# GankenKunCircuit.net
KiCad netlist of a schematic drawn in EAGLE
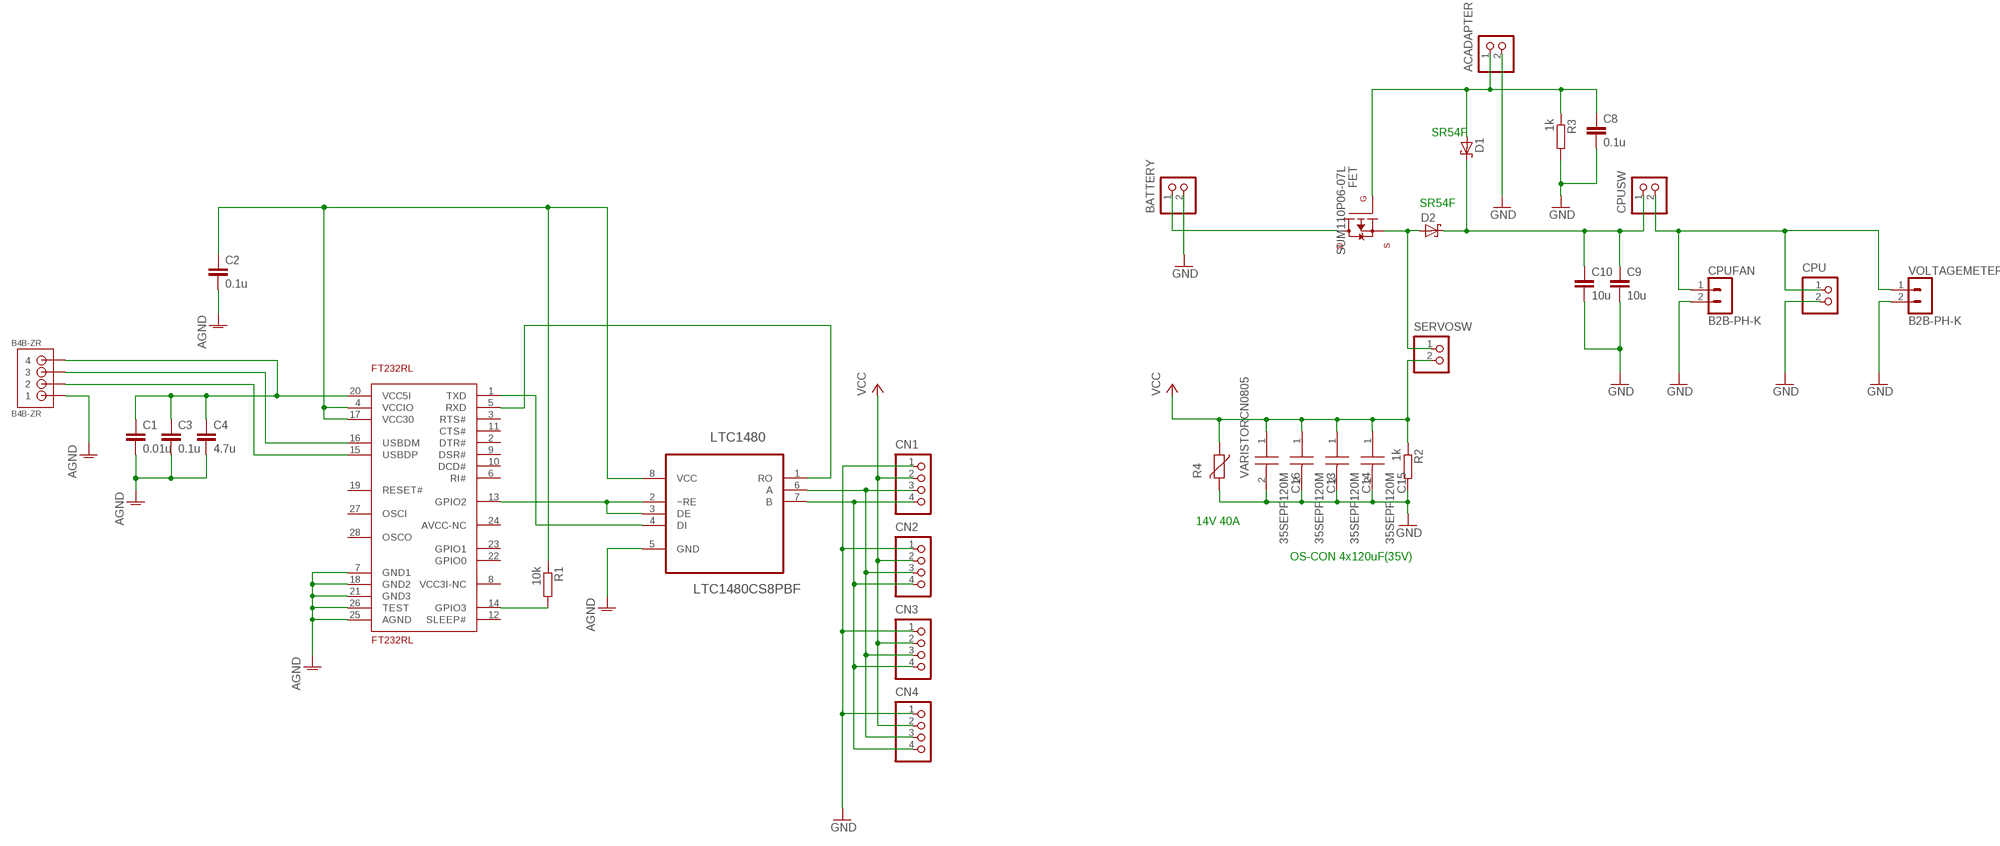
[diagram p0: schematic, sheet 1]

(export (version "E")
  (design (tool "Eeschema 10.0.6"))
  (components
    (comp (ref "ACADAPTER")
      (value "B2B-XH-A")
      (footprint "eagle-import:B2B-XH-A")
      (libsource (lib "eagle-import") (part "B2B-XH-A"))
    )
    (comp (ref "B4B-ZR")
      (value "B4B-ZR")
      (footprint "eagle-import:B4B-ZR")
      (libsource (lib "eagle-import") (part "B4B-ZR"))
    )
    (comp (ref "BATTERY")
      (value "B2P-VH")
      (footprint "eagle-import:B2P-VH")
      (libsource (lib "eagle-import") (part "B2P-VH"))
    )
    (comp (ref "C1")
      (value "0.01u")
      (footprint "eagle-import:C2012")
      (libsource (lib "eagle-import") (part "C-EUC2012"))
    )
    (comp (ref "C2")
      (value "0.1u")
      (footprint "eagle-import:C2012")
      (libsource (lib "eagle-import") (part "C-EUC2012"))
    )
    (comp (ref "C3")
      (value "0.1u")
      (footprint "eagle-import:C2012")
      (libsource (lib "eagle-import") (part "C-EUC2012"))
    )
    (comp (ref "C4")
      (value "4.7u")
      (footprint "eagle-import:C2012")
      (libsource (lib "eagle-import") (part "C-EUC2012"))
    )
    (comp (ref "C8")
      (value "0.1u")
      (footprint "eagle-import:C2012")
      (libsource (lib "eagle-import") (part "C-EUC2012"))
    )
    (comp (ref "C9")
      (value "10u")
      (footprint "eagle-import:C3216")
      (libsource (lib "eagle-import") (part "C-EUC3216"))
    )
    (comp (ref "C10")
      (value "10u")
      (footprint "eagle-import:C3216")
      (libsource (lib "eagle-import") (part "C-EUC3216"))
    )
    (comp (ref "C13")
      (value "35SEPF120M")
      (footprint "eagle-import:CAPPRD500W65D1000H1350")
      (fields (field (name "MOUSER_PART_NUMBER") "667-35SEPF120M") (field (name "RS_PART_NUMBER") "1000082"))
      (libsource (lib "eagle-import") (part "35SEPF120M"))
    )
    (comp (ref "C14")
      (value "35SEPF120M")
      (footprint "eagle-import:CAPPRD500W65D1000H1350")
      (fields (field (name "MOUSER_PART_NUMBER") "667-35SEPF120M") (field (name "RS_PART_NUMBER") "1000082"))
      (libsource (lib "eagle-import") (part "35SEPF120M"))
    )
    (comp (ref "C15")
      (value "35SEPF120M")
      (footprint "eagle-import:CAPPRD500W65D1000H1350")
      (fields (field (name "MOUSER_PART_NUMBER") "667-35SEPF120M") (field (name "RS_PART_NUMBER") "1000082"))
      (libsource (lib "eagle-import") (part "35SEPF120M"))
    )
    (comp (ref "C16")
      (value "35SEPF120M")
      (footprint "eagle-import:CAPPRD500W65D1000H1350")
      (fields (field (name "MOUSER_PART_NUMBER") "667-35SEPF120M") (field (name "RS_PART_NUMBER") "1000082"))
      (libsource (lib "eagle-import") (part "35SEPF120M"))
    )
    (comp (ref "CN1")
      (value "B4B-XH-A")
      (footprint "eagle-import:B4B-XH-A")
      (libsource (lib "eagle-import") (part "B4B-XH-A"))
    )
    (comp (ref "CN2")
      (value "B4B-XH-A")
      (footprint "eagle-import:B4B-XH-A")
      (libsource (lib "eagle-import") (part "B4B-XH-A"))
    )
    (comp (ref "CN3")
      (value "B4B-XH-A")
      (footprint "eagle-import:B4B-XH-A")
      (libsource (lib "eagle-import") (part "B4B-XH-A"))
    )
    (comp (ref "CN4")
      (value "B4B-XH-A")
      (footprint "eagle-import:B4B-XH-A")
      (libsource (lib "eagle-import") (part "B4B-XH-A"))
    )
    (comp (ref "CPU")
      (value "B2B-XH-A")
      (footprint "eagle-import:B2B-XH-A")
      (libsource (lib "eagle-import") (part "B2B-XH-A"))
    )
    (comp (ref "CPUFAN")
      (value "B2B-PH-K")
      (footprint "eagle-import:B2B-PH-K")
      (libsource (lib "eagle-import") (part "B2B-PH-K"))
    )
    (comp (ref "CPUSW")
      (value "B2B-XH-A")
      (footprint "eagle-import:B2B-XH-A")
      (libsource (lib "eagle-import") (part "B2B-XH-A"))
    )
    (comp (ref "D1")
      (value "SCHOTTKY-DIODESMD")
      (footprint "eagle-import:SMB")
      (libsource (lib "eagle-import") (part "SCHOTTKY-DIODESMD"))
    )
    (comp (ref "D2")
      (value "SCHOTTKY-DIODESMD")
      (footprint "eagle-import:SMB")
      (libsource (lib "eagle-import") (part "SCHOTTKY-DIODESMD"))
    )
    (comp (ref "FET")
      (value "SUM110P06-07L")
      (footprint "eagle-import:TO-263-2")
      (fields (field (name "MF") "Vishay"))
      (libsource (lib "eagle-import") (part "SUM110P06-07L"))
    )
    (comp (ref "FT232RL")
      (value "FT232RL")
      (footprint "eagle-import:SSOP28")
      (fields (field (name "MF") "FTDI"))
      (libsource (lib "eagle-import") (part "FT232RL"))
    )
    (comp (ref "LTC1480")
      (value "LTC1480CS8PBF")
      (footprint "eagle-import:SOIC127P600X175-8N")
      (fields (field (name "MF") "Linear Technology/Analog") (field (name "MP") "LTC1480CS8#PBF"))
      (libsource (lib "eagle-import") (part "LTC1480CS8PBF"))
    )
    (comp (ref "R1")
      (value "10k")
      (footprint "eagle-import:M2012")
      (libsource (lib "eagle-import") (part "R-EU_M2012"))
    )
    (comp (ref "R2")
      (value "1k")
      (footprint "eagle-import:M2012")
      (libsource (lib "eagle-import") (part "R-EU_M2012"))
    )
    (comp (ref "R3")
      (value "1k")
      (footprint "eagle-import:M2012")
      (libsource (lib "eagle-import") (part "R-EU_M2012"))
    )
    (comp (ref "R4")
      (value "VARISTORCN0805")
      (footprint "eagle-import:CT_CN0805")
      (libsource (lib "eagle-import") (part "VARISTORCN0805"))
    )
    (comp (ref "SERVOSW")
      (value "B2P-VH")
      (footprint "eagle-import:B2P-VH")
      (libsource (lib "eagle-import") (part "B2P-VH"))
    )
    (comp (ref "VOLTAGEMETER")
      (value "B2B-PH-K")
      (footprint "eagle-import:B2B-PH-K")
      (libsource (lib "eagle-import") (part "B2B-PH-K"))
    )
  )
  (nets
    (net (code "1") (name "AGND") (class "Default")
      (node (ref "B4B-ZR") (pin "1") (pinfunction "1_1") (pintype "bidirectional"))
      (node (ref "C1") (pin "2") (pinfunction "2_2") (pintype "passive"))
      (node (ref "C2") (pin "2") (pinfunction "2_2") (pintype "passive"))
      (node (ref "C3") (pin "2") (pinfunction "2_2") (pintype "passive"))
      (node (ref "C4") (pin "2") (pinfunction "2_2") (pintype "passive"))
      (node (ref "FT232RL") (pin "18") (pinfunction "GND2_18") (pintype "power_in"))
      (node (ref "FT232RL") (pin "21") (pinfunction "GND3_21") (pintype "power_in"))
      (node (ref "FT232RL") (pin "25") (pinfunction "AGND_25") (pintype "power_in"))
      (node (ref "FT232RL") (pin "26") (pinfunction "TEST_26") (pintype "input"))
      (node (ref "FT232RL") (pin "7") (pinfunction "GND1_7") (pintype "power_in"))
      (node (ref "LTC1480") (pin "5") (pinfunction "GND_5") (pintype "passive"))
    )
    (net (code "2") (name "GND") (class "Default")
      (node (ref "ACADAPTER") (pin "2") (pinfunction "2_2") (pintype "passive"))
      (node (ref "BATTERY") (pin "2") (pinfunction "2_2") (pintype "passive"))
      (node (ref "C10") (pin "2") (pinfunction "2_2") (pintype "passive"))
      (node (ref "C13") (pin "2") (pinfunction "-_2") (pintype "bidirectional"))
      (node (ref "C14") (pin "2") (pinfunction "-_2") (pintype "bidirectional"))
      (node (ref "C15") (pin "2") (pinfunction "-_2") (pintype "bidirectional"))
      (node (ref "C16") (pin "2") (pinfunction "-_2") (pintype "bidirectional"))
      (node (ref "C8") (pin "2") (pinfunction "2_2") (pintype "passive"))
      (node (ref "C9") (pin "2") (pinfunction "2_2") (pintype "passive"))
      (node (ref "CN1") (pin "1") (pinfunction "1_1") (pintype "passive"))
      (node (ref "CN2") (pin "1") (pinfunction "1_1") (pintype "passive"))
      (node (ref "CN3") (pin "1") (pinfunction "1_1") (pintype "passive"))
      (node (ref "CN4") (pin "1") (pinfunction "1_1") (pintype "passive"))
      (node (ref "CPU") (pin "2") (pinfunction "2_2") (pintype "passive"))
      (node (ref "CPUFAN") (pin "2") (pinfunction "2_2") (pintype "passive"))
      (node (ref "R2") (pin "2") (pinfunction "2_2") (pintype "passive"))
      (node (ref "R3") (pin "2") (pinfunction "2_2") (pintype "passive"))
      (node (ref "R4") (pin "2") (pinfunction "2_2") (pintype "passive"))
      (node (ref "VOLTAGEMETER") (pin "2") (pinfunction "2_2") (pintype "passive"))
    )
    (net (code "3") (name "Net-(C10-Pad1)") (class "Default")
      (node (ref "C10") (pin "1") (pinfunction "1_1") (pintype "passive"))
      (node (ref "C9") (pin "1") (pinfunction "1_1") (pintype "passive"))
      (node (ref "CPUSW") (pin "1") (pinfunction "1_1") (pintype "passive"))
      (node (ref "D1") (pin "C") (pinfunction "C_C") (pintype "passive"))
      (node (ref "D2") (pin "C") (pinfunction "C_C") (pintype "passive"))
    )
    (net (code "4") (name "Net-(CPU-Pad1)") (class "Default")
      (node (ref "CPU") (pin "1") (pinfunction "1_1") (pintype "passive"))
      (node (ref "CPUFAN") (pin "1") (pinfunction "1_1") (pintype "passive"))
      (node (ref "CPUSW") (pin "2") (pinfunction "2_2") (pintype "passive"))
      (node (ref "VOLTAGEMETER") (pin "1") (pinfunction "1_1") (pintype "passive"))
    )
    (net (code "5") (name "Net-(FET-D)") (class "Default")
      (node (ref "BATTERY") (pin "1") (pinfunction "1_1") (pintype "passive"))
      (node (ref "FET") (pin "4") (pinfunction "D_4") (pintype "passive"))
    )
    (net (code "6") (name "Net-(FET-G)") (class "Default")
      (node (ref "ACADAPTER") (pin "1") (pinfunction "1_1") (pintype "passive"))
      (node (ref "C8") (pin "1") (pinfunction "1_1") (pintype "passive"))
      (node (ref "D1") (pin "A") (pinfunction "A_A") (pintype "passive"))
      (node (ref "FET") (pin "1") (pinfunction "G_1") (pintype "passive"))
      (node (ref "R3") (pin "1") (pinfunction "1_1") (pintype "passive"))
    )
    (net (code "7") (name "Net-(FET-S)") (class "Default")
      (node (ref "D2") (pin "A") (pinfunction "A_A") (pintype "passive"))
      (node (ref "FET") (pin "3") (pinfunction "S_3") (pintype "passive"))
      (node (ref "SERVOSW") (pin "1") (pinfunction "1_1") (pintype "passive"))
    )
    (net (code "8") (name "Net-(FT232RL-GPIO2)") (class "Default")
      (node (ref "FT232RL") (pin "13") (pinfunction "GPIO2_13") (pintype "output"))
      (node (ref "LTC1480") (pin "2") (pinfunction "~{RE}_2") (pintype "input"))
      (node (ref "LTC1480") (pin "3") (pinfunction "DE_3") (pintype "input"))
    )
    (net (code "9") (name "Net-(FT232RL-GPIO3)") (class "Default")
      (node (ref "FT232RL") (pin "14") (pinfunction "GPIO3_14") (pintype "input"))
      (node (ref "R1") (pin "2") (pinfunction "2_2") (pintype "passive"))
    )
    (net (code "10") (name "Net-(FT232RL-RXD)") (class "Default")
      (node (ref "FT232RL") (pin "5") (pinfunction "RXD_5") (pintype "input"))
      (node (ref "LTC1480") (pin "1") (pinfunction "RO_1") (pintype "output"))
    )
    (net (code "11") (name "Net-(FT232RL-TXD)") (class "Default")
      (node (ref "FT232RL") (pin "1") (pinfunction "TXD_1") (pintype "output"))
      (node (ref "LTC1480") (pin "4") (pinfunction "DI_4") (pintype "input"))
    )
    (net (code "12") (name "Net-(FT232RL-USBDM)") (class "Default")
      (node (ref "B4B-ZR") (pin "3") (pinfunction "3_3") (pintype "bidirectional"))
      (node (ref "FT232RL") (pin "16") (pinfunction "USBDM_16") (pintype "bidirectional"))
    )
    (net (code "13") (name "Net-(FT232RL-USBDP)") (class "Default")
      (node (ref "B4B-ZR") (pin "2") (pinfunction "2_2") (pintype "bidirectional"))
      (node (ref "FT232RL") (pin "15") (pinfunction "USBDP_15") (pintype "bidirectional"))
    )
    (net (code "14") (name "Net-(FT232RL-VCC5I)") (class "Default")
      (node (ref "B4B-ZR") (pin "4") (pinfunction "4_4") (pintype "bidirectional"))
      (node (ref "C1") (pin "1") (pinfunction "1_1") (pintype "passive"))
      (node (ref "C3") (pin "1") (pinfunction "1_1") (pintype "passive"))
      (node (ref "C4") (pin "1") (pinfunction "1_1") (pintype "passive"))
      (node (ref "FT232RL") (pin "20") (pinfunction "VCC5I_20") (pintype "power_in"))
    )
    (net (code "15") (name "Net-(FT232RL-VCC30)") (class "Default")
      (node (ref "C2") (pin "1") (pinfunction "1_1") (pintype "passive"))
      (node (ref "FT232RL") (pin "17") (pinfunction "VCC30_17") (pintype "power_in"))
      (node (ref "FT232RL") (pin "4") (pinfunction "VCCIO_4") (pintype "power_in"))
      (node (ref "LTC1480") (pin "8") (pinfunction "VCC_8") (pintype "power_in"))
      (node (ref "R1") (pin "1") (pinfunction "1_1") (pintype "passive"))
    )
    (net (code "16") (name "Net-(LTC1480-A)") (class "Default")
      (node (ref "CN1") (pin "3") (pinfunction "3_3") (pintype "passive"))
      (node (ref "CN2") (pin "3") (pinfunction "3_3") (pintype "passive"))
      (node (ref "CN3") (pin "3") (pinfunction "3_3") (pintype "passive"))
      (node (ref "CN4") (pin "3") (pinfunction "3_3") (pintype "passive"))
      (node (ref "LTC1480") (pin "6") (pinfunction "A_6") (pintype "bidirectional"))
    )
    (net (code "17") (name "Net-(LTC1480-B)") (class "Default")
      (node (ref "CN1") (pin "4") (pinfunction "4_4") (pintype "passive"))
      (node (ref "CN2") (pin "4") (pinfunction "4_4") (pintype "passive"))
      (node (ref "CN3") (pin "4") (pinfunction "4_4") (pintype "passive"))
      (node (ref "CN4") (pin "4") (pinfunction "4_4") (pintype "passive"))
      (node (ref "LTC1480") (pin "7") (pinfunction "B_7") (pintype "bidirectional"))
    )
    (net (code "18") (name "VCC") (class "Default")
      (node (ref "C13") (pin "1") (pinfunction "+_1") (pintype "bidirectional"))
      (node (ref "C14") (pin "1") (pinfunction "+_1") (pintype "bidirectional"))
      (node (ref "C15") (pin "1") (pinfunction "+_1") (pintype "bidirectional"))
      (node (ref "C16") (pin "1") (pinfunction "+_1") (pintype "bidirectional"))
      (node (ref "CN1") (pin "2") (pinfunction "2_2") (pintype "passive"))
      (node (ref "CN2") (pin "2") (pinfunction "2_2") (pintype "passive"))
      (node (ref "CN3") (pin "2") (pinfunction "2_2") (pintype "passive"))
      (node (ref "CN4") (pin "2") (pinfunction "2_2") (pintype "passive"))
      (node (ref "R2") (pin "1") (pinfunction "1_1") (pintype "passive"))
      (node (ref "R4") (pin "1") (pinfunction "1_1") (pintype "passive"))
      (node (ref "SERVOSW") (pin "2") (pinfunction "2_2") (pintype "passive"))
    )
    (net (code "19") (name "unconnected-(FT232RL-AVCC-NC-Pad24)") (class "Default")
      (node (ref "FT232RL") (pin "24") (pinfunction "AVCC-NC_24") (pintype "no_connect"))
    )
    (net (code "20") (name "unconnected-(FT232RL-CTS#-Pad11)") (class "Default")
      (node (ref "FT232RL") (pin "11") (pinfunction "CTS#_11") (pintype "input"))
    )
    (net (code "21") (name "unconnected-(FT232RL-DCD#-Pad10)") (class "Default")
      (node (ref "FT232RL") (pin "10") (pinfunction "DCD#_10") (pintype "input"))
    )
    (net (code "22") (name "unconnected-(FT232RL-DSR#-Pad9)") (class "Default")
      (node (ref "FT232RL") (pin "9") (pinfunction "DSR#_9") (pintype "input"))
    )
    (net (code "23") (name "unconnected-(FT232RL-DTR#-Pad2)") (class "Default")
      (node (ref "FT232RL") (pin "2") (pinfunction "DTR#_2") (pintype "output"))
    )
    (net (code "24") (name "unconnected-(FT232RL-GPIO0-Pad22)") (class "Default")
      (node (ref "FT232RL") (pin "22") (pinfunction "GPIO0_22") (pintype "output"))
    )
    (net (code "25") (name "unconnected-(FT232RL-GPIO1-Pad23)") (class "Default")
      (node (ref "FT232RL") (pin "23") (pinfunction "GPIO1_23") (pintype "output"))
    )
    (net (code "26") (name "unconnected-(FT232RL-OSCI-Pad27)") (class "Default")
      (node (ref "FT232RL") (pin "27") (pinfunction "OSCI_27") (pintype "input"))
    )
    (net (code "27") (name "unconnected-(FT232RL-OSCO-Pad28)") (class "Default")
      (node (ref "FT232RL") (pin "28") (pinfunction "OSCO_28") (pintype "output"))
    )
    (net (code "28") (name "unconnected-(FT232RL-RESET#-Pad19)") (class "Default")
      (node (ref "FT232RL") (pin "19") (pinfunction "RESET#_19") (pintype "input"))
    )
    (net (code "29") (name "unconnected-(FT232RL-RI#-Pad6)") (class "Default")
      (node (ref "FT232RL") (pin "6") (pinfunction "RI#_6") (pintype "input"))
    )
    (net (code "30") (name "unconnected-(FT232RL-RTS#-Pad3)") (class "Default")
      (node (ref "FT232RL") (pin "3") (pinfunction "RTS#_3") (pintype "output"))
    )
    (net (code "31") (name "unconnected-(FT232RL-SLEEP#-Pad12)") (class "Default")
      (node (ref "FT232RL") (pin "12") (pinfunction "SLEEP#_12") (pintype "input"))
    )
    (net (code "32") (name "unconnected-(FT232RL-VCC3I-NC-Pad8)") (class "Default")
      (node (ref "FT232RL") (pin "8") (pinfunction "VCC3I-NC_8") (pintype "no_connect"))
    )
  )
)
